# 2018_FDP_PROPULSION.net
KiCad netlist of a schematic drawn in Altium Designer
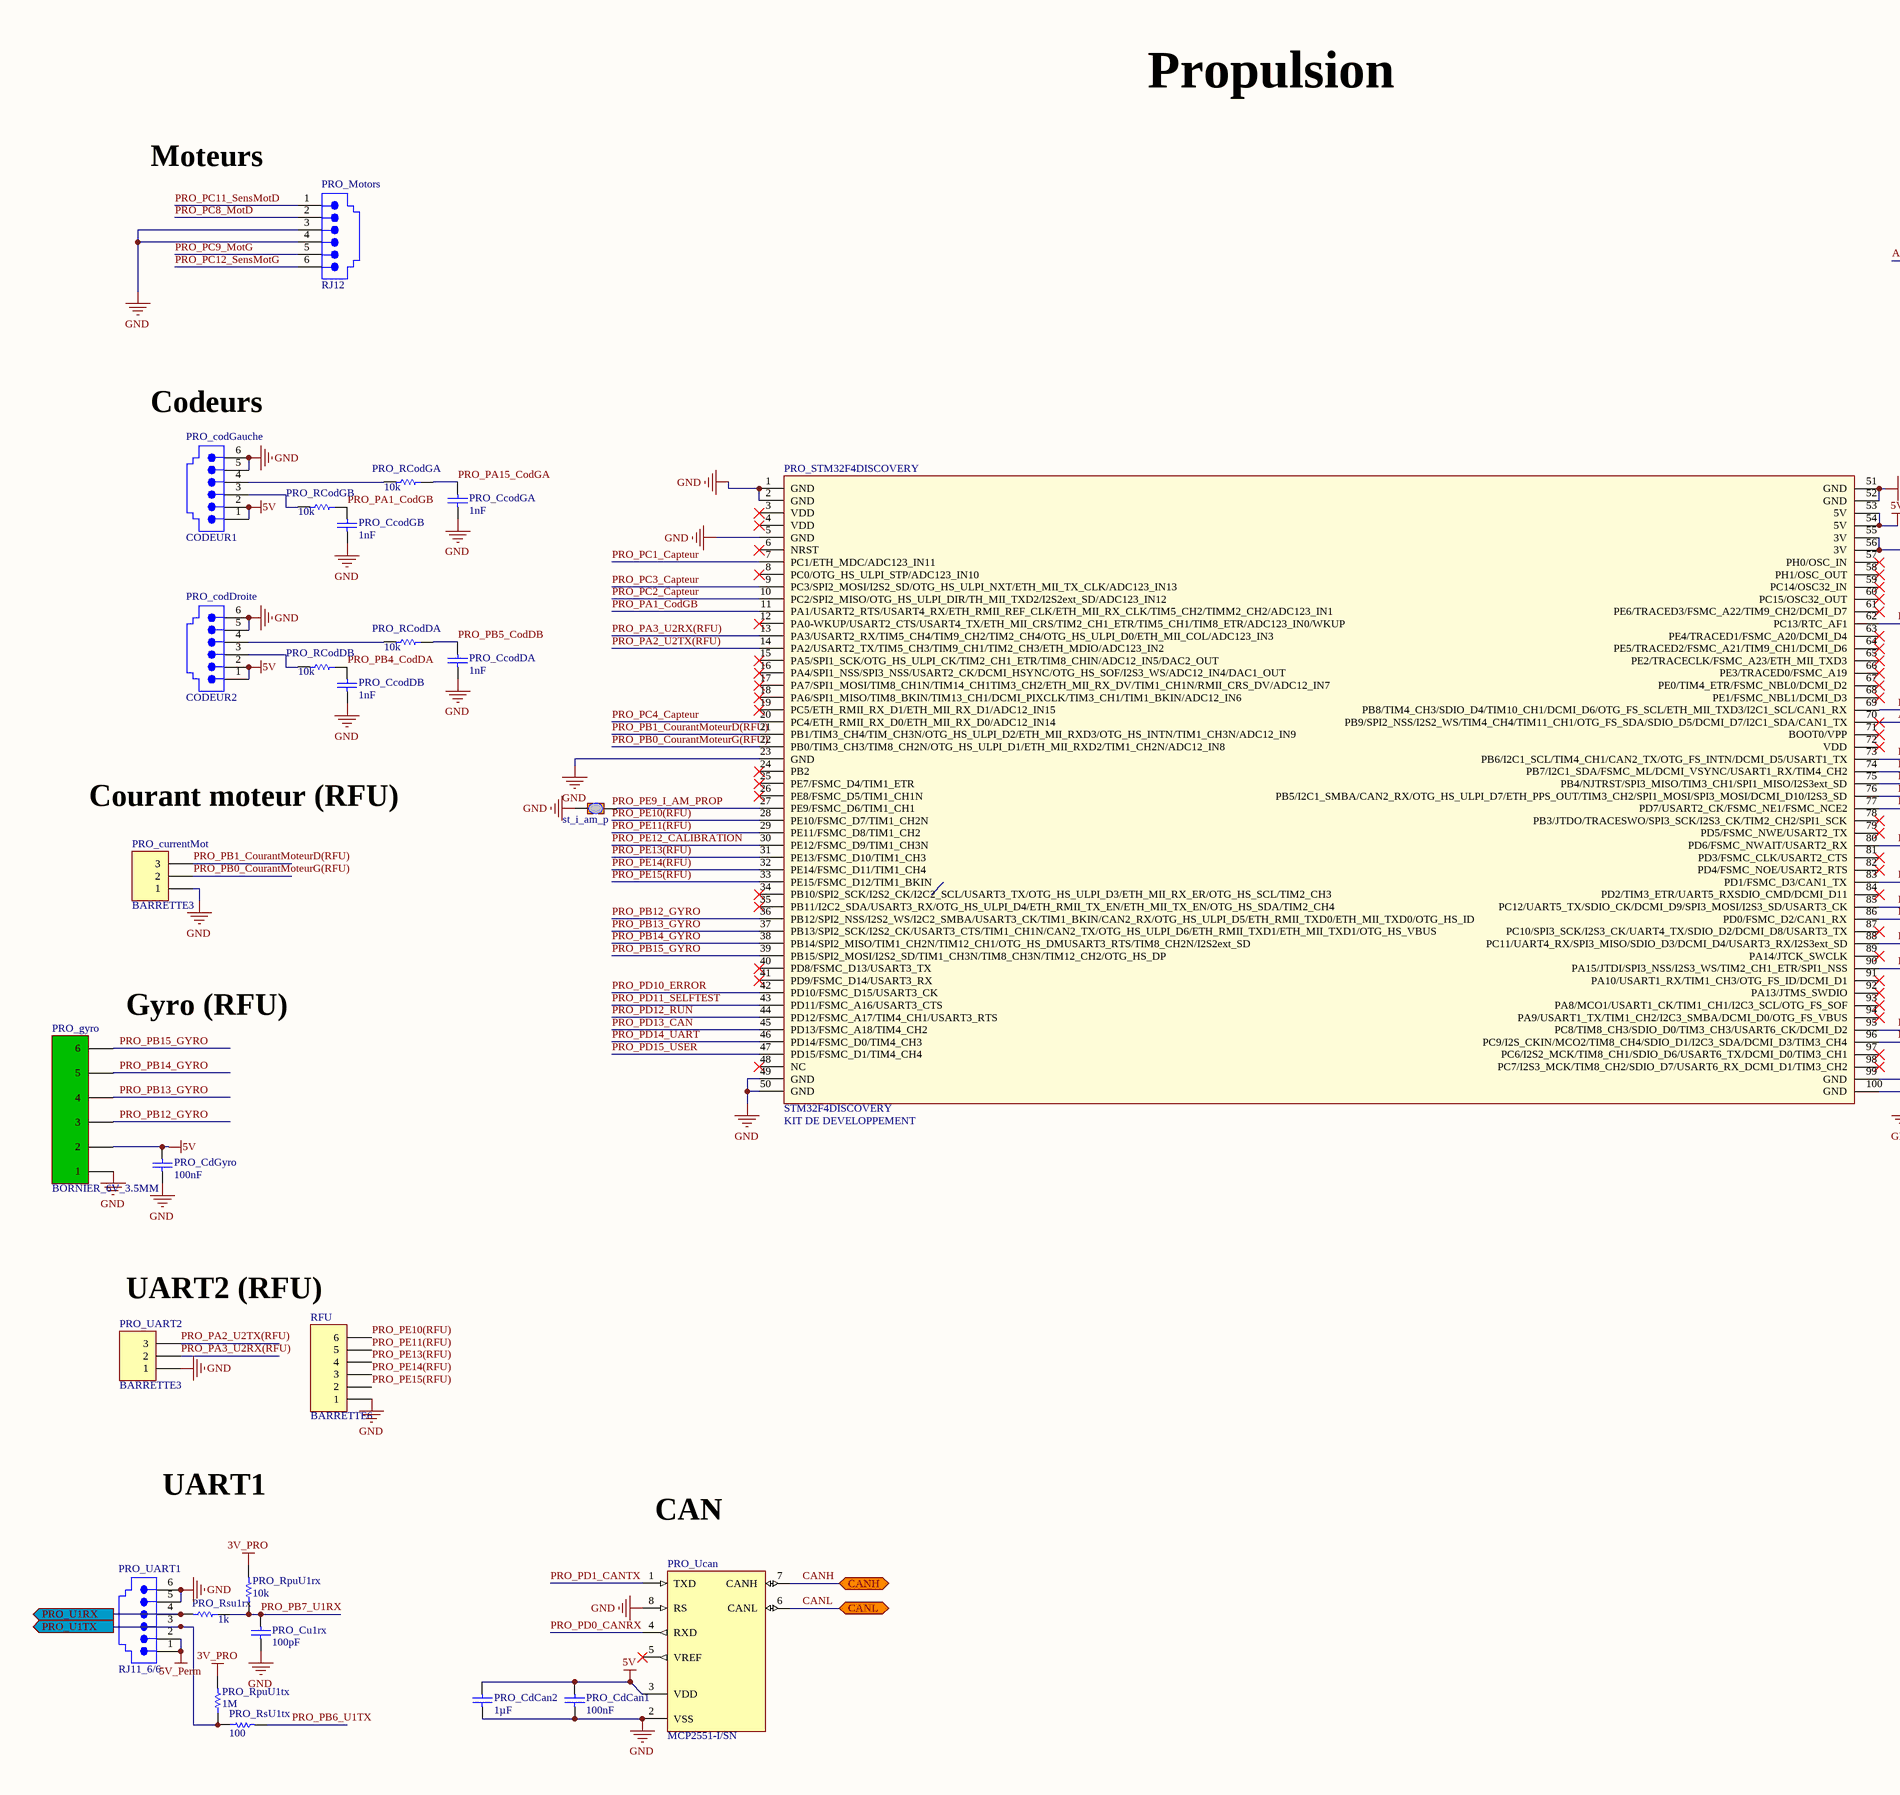
[diagram p0: 2018_FDP_PROPULSION.SchDoc, left]
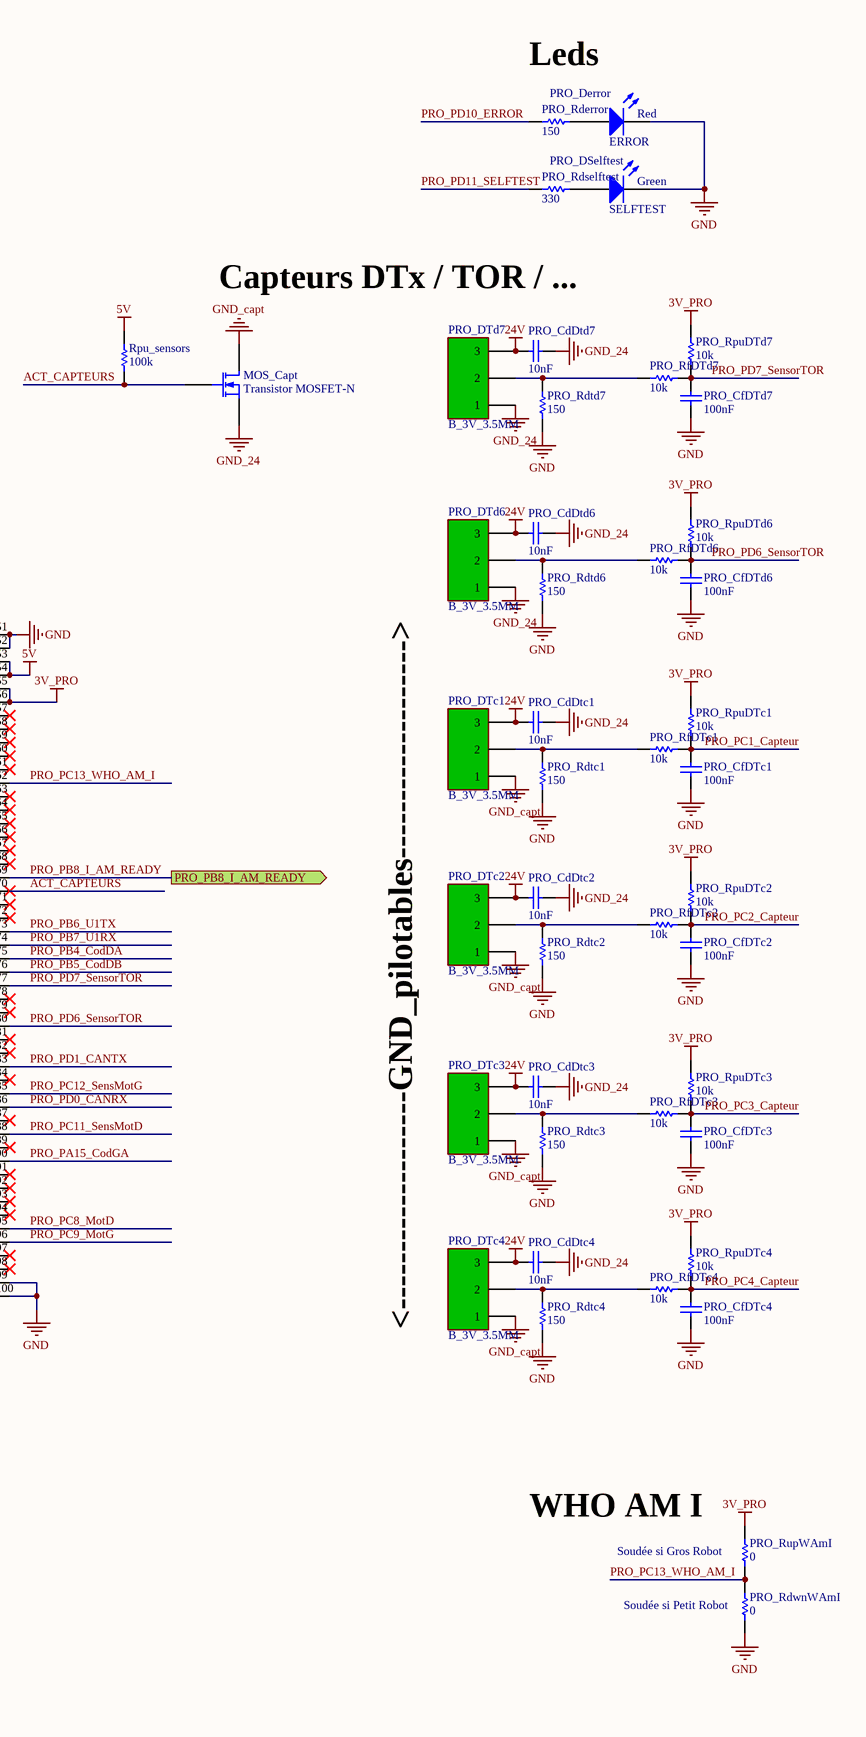
[diagram p1: 2018_FDP_PROPULSION.SchDoc, right]

(export (version "E")
  (design (tool "Eeschema 10.0.6"))
  (components
    (comp (ref "MOS_Capt")
      (value "Transistor MOSFET-N")
      (footprint "SOT23-3N")
      (description "N-Channel MOSFET")
      (fields (field (name "PUBLISHER") "Altium Limited"))
      (libsource (lib "_ROBOT") (part "Transistor MOSFET-N"))
    )
    (comp (ref "PRO_CcodDA")
      (value "1nF")
      (footprint "C0805_N")
      (description "Capacitor")
      (fields (field (name "PUBLISHER") "Altium Limited"))
      (libsource (lib "_ROBOT") (part "Condensateur"))
    )
    (comp (ref "PRO_CcodDB")
      (value "1nF")
      (footprint "C0805_N")
      (description "Capacitor")
      (fields (field (name "PUBLISHER") "Altium Limited"))
      (libsource (lib "_ROBOT") (part "Condensateur"))
    )
    (comp (ref "PRO_CcodGA")
      (value "1nF")
      (footprint "C0805_N")
      (description "Capacitor")
      (fields (field (name "PUBLISHER") "Altium Limited"))
      (libsource (lib "_ROBOT") (part "Condensateur"))
    )
    (comp (ref "PRO_CcodGB")
      (value "1nF")
      (footprint "C0805_N")
      (description "Capacitor")
      (fields (field (name "PUBLISHER") "Altium Limited"))
      (libsource (lib "_ROBOT") (part "Condensateur"))
    )
    (comp (ref "PRO_CdCan1")
      (value "100nF")
      (footprint "C0805_N")
      (description "Capacitor")
      (fields (field (name "PUBLISHER") "Altium Limited"))
      (libsource (lib "_ROBOT") (part "Condensateur"))
    )
    (comp (ref "PRO_CdCan2")
      (value "1µF")
      (footprint "C0805_N")
      (description "Capacitor")
      (fields (field (name "PUBLISHER") "Altium Limited"))
      (libsource (lib "_ROBOT") (part "Condensateur"))
    )
    (comp (ref "PRO_CdDtc1")
      (value "10nF")
      (footprint "C0805_N")
      (description "Capacitor")
      (fields (field (name "PUBLISHER") "Altium Limited"))
      (libsource (lib "_ROBOT") (part "Condensateur"))
    )
    (comp (ref "PRO_CdDtc2")
      (value "10nF")
      (footprint "C0805_N")
      (description "Capacitor")
      (fields (field (name "PUBLISHER") "Altium Limited"))
      (libsource (lib "_ROBOT") (part "Condensateur"))
    )
    (comp (ref "PRO_CdDtc3")
      (value "10nF")
      (footprint "C0805_N")
      (description "Capacitor")
      (fields (field (name "PUBLISHER") "Altium Limited"))
      (libsource (lib "_ROBOT") (part "Condensateur"))
    )
    (comp (ref "PRO_CdDtc4")
      (value "10nF")
      (footprint "C0805_N")
      (description "Capacitor")
      (fields (field (name "PUBLISHER") "Altium Limited"))
      (libsource (lib "_ROBOT") (part "Condensateur"))
    )
    (comp (ref "PRO_CdDtd6")
      (value "10nF")
      (footprint "C0805_N")
      (description "Capacitor")
      (fields (field (name "PUBLISHER") "Altium Limited"))
      (libsource (lib "_ROBOT") (part "Condensateur"))
    )
    (comp (ref "PRO_CdDtd7")
      (value "10nF")
      (footprint "C0805_N")
      (description "Capacitor")
      (fields (field (name "PUBLISHER") "Altium Limited"))
      (libsource (lib "_ROBOT") (part "Condensateur"))
    )
    (comp (ref "PRO_CdGyro")
      (value "100nF")
      (footprint "C0805_N")
      (description "Capacitor")
      (fields (field (name "PUBLISHER") "Altium Limited"))
      (libsource (lib "_ROBOT") (part "Condensateur"))
    )
    (comp (ref "PRO_CfDTc1")
      (value "100nF")
      (footprint "C0805_N")
      (description "Capacitor")
      (fields (field (name "PUBLISHER") "Altium Limited"))
      (libsource (lib "_ROBOT") (part "Condensateur"))
    )
    (comp (ref "PRO_CfDTc2")
      (value "100nF")
      (footprint "C0805_N")
      (description "Capacitor")
      (fields (field (name "PUBLISHER") "Altium Limited"))
      (libsource (lib "_ROBOT") (part "Condensateur"))
    )
    (comp (ref "PRO_CfDTc3")
      (value "100nF")
      (footprint "C0805_N")
      (description "Capacitor")
      (fields (field (name "PUBLISHER") "Altium Limited"))
      (libsource (lib "_ROBOT") (part "Condensateur"))
    )
    (comp (ref "PRO_CfDTc4")
      (value "100nF")
      (footprint "C0805_N")
      (description "Capacitor")
      (fields (field (name "PUBLISHER") "Altium Limited"))
      (libsource (lib "_ROBOT") (part "Condensateur"))
    )
    (comp (ref "PRO_CfDTd6")
      (value "100nF")
      (footprint "C0805_N")
      (description "Capacitor")
      (fields (field (name "PUBLISHER") "Altium Limited"))
      (libsource (lib "_ROBOT") (part "Condensateur"))
    )
    (comp (ref "PRO_CfDTd7")
      (value "100nF")
      (footprint "C0805_N")
      (description "Capacitor")
      (fields (field (name "PUBLISHER") "Altium Limited"))
      (libsource (lib "_ROBOT") (part "Condensateur"))
    )
    (comp (ref "PRO_codDroite")
      (value "CODEUR2")
      (footprint "RJ11_6/6 - droit")
      (description "Right Angle, Standard Profile, Offset Latch DECconnect, Flangeless PCB Jack")
      (fields (field (name "PUBLISHER") "Altium Limited"))
      (libsource (lib "miniprojet") (part "RJ11_6/6"))
    )
    (comp (ref "PRO_codGauche")
      (value "CODEUR1")
      (footprint "RJ11_6/6 - droit")
      (description "Right Angle, Standard Profile, Offset Latch DECconnect, Flangeless PCB Jack")
      (fields (field (name "PUBLISHER") "Altium Limited"))
      (libsource (lib "miniprojet") (part "RJ11_6/6"))
    )
    (comp (ref "PRO_Cu1rx")
      (value "100pF")
      (footprint "C0805_N")
      (description "Capacitor")
      (fields (field (name "PUBLISHER") "Altium Limited"))
      (libsource (lib "_ROBOT") (part "Condensateur"))
    )
    (comp (ref "PRO_currentMot")
      (value "BARRETTE3")
      (footprint "HE14_3")
      (description "Header, 3-Pin")
      (fields (field (name "PUBLISHER") "Altium Limited"))
      (libsource (lib "Connecteur") (part "BARRETTE3"))
    )
    (comp (ref "PRO_Derror")
      (value "ERROR")
      (footprint "LED_0805")
      (description "Typical LED")
      (fields (field (name "PUBLISHER") "Altium Limited"))
      (libsource (lib "_ROBOT") (part "LED"))
    )
    (comp (ref "PRO_DSelftest")
      (value "SELFTEST")
      (footprint "LED_0805")
      (description "Typical LED")
      (fields (field (name "PUBLISHER") "Altium Limited"))
      (libsource (lib "_ROBOT") (part "LED"))
    )
    (comp (ref "PRO_DTc1")
      (value "B_3V_3.5MM")
      (footprint "BORNIER_3V_3.5MM")
      (libsource (lib "Connecteur") (part "BORNIER_3V_3.5MM"))
    )
    (comp (ref "PRO_DTc2")
      (value "B_3V_3.5MM")
      (footprint "BORNIER_3V_3.5MM")
      (libsource (lib "Connecteur") (part "BORNIER_3V_3.5MM"))
    )
    (comp (ref "PRO_DTc3")
      (value "B_3V_3.5MM")
      (footprint "BORNIER_3V_3.5MM")
      (libsource (lib "Connecteur") (part "BORNIER_3V_3.5MM"))
    )
    (comp (ref "PRO_DTc4")
      (value "B_3V_3.5MM")
      (footprint "BORNIER_3V_3.5MM")
      (libsource (lib "Connecteur") (part "BORNIER_3V_3.5MM"))
    )
    (comp (ref "PRO_DTd6")
      (value "B_3V_3.5MM")
      (footprint "BORNIER_3V_3.5MM")
      (libsource (lib "Connecteur") (part "BORNIER_3V_3.5MM"))
    )
    (comp (ref "PRO_DTd7")
      (value "B_3V_3.5MM")
      (footprint "BORNIER_3V_3.5MM")
      (libsource (lib "Connecteur") (part "BORNIER_3V_3.5MM"))
    )
    (comp (ref "PRO_gyro")
      (value "BORNIER_6V_3.5MM")
      (footprint "BORNIER_6V_3.5MM")
      (libsource (lib "Connecteur") (part "BORNIER_6V_3.5MM"))
    )
    (comp (ref "PRO_Motors")
      (value "RJ12")
      (footprint "RJ11_6/6 - droit")
      (description "Right Angle, Standard Profile, Offset Latch DECconnect, Flangeless PCB Jack")
      (fields (field (name "PUBLISHER") "Altium Limited"))
      (libsource (lib "Connecteur") (part "RJ11_6/6"))
    )
    (comp (ref "PRO_RCodDA")
      (value "10k")
      (footprint "R1206_N")
      (description "Resistor")
      (fields (field (name "PUBLISHER") "Altium Limited"))
      (libsource (lib "_ROBOT") (part "Resistor"))
    )
    (comp (ref "PRO_RCodDB")
      (value "10k")
      (footprint "R1206_N")
      (description "Resistor")
      (fields (field (name "PUBLISHER") "Altium Limited"))
      (libsource (lib "_ROBOT") (part "Resistor"))
    )
    (comp (ref "PRO_RCodGA")
      (value "10k")
      (footprint "R1206_N")
      (description "Resistor")
      (fields (field (name "PUBLISHER") "Altium Limited"))
      (libsource (lib "_ROBOT") (part "Resistor"))
    )
    (comp (ref "PRO_RCodGB")
      (value "10k")
      (footprint "R1206_N")
      (description "Resistor")
      (fields (field (name "PUBLISHER") "Altium Limited"))
      (libsource (lib "_ROBOT") (part "Resistor"))
    )
    (comp (ref "PRO_Rderror")
      (value "150")
      (footprint "R1206_N")
      (description "Resistor")
      (fields (field (name "PUBLISHER") "Altium Limited"))
      (libsource (lib "_ROBOT") (part "Resistor"))
    )
    (comp (ref "PRO_Rdselftest")
      (value "330")
      (footprint "R1206_N")
      (description "Resistor")
      (fields (field (name "PUBLISHER") "Altium Limited"))
      (libsource (lib "_ROBOT") (part "Resistor"))
    )
    (comp (ref "PRO_Rdtc1")
      (value "150")
      (footprint "R1206_N")
      (description "Resistor")
      (fields (field (name "PUBLISHER") "Altium Limited"))
      (libsource (lib "_ROBOT") (part "Resistor"))
    )
    (comp (ref "PRO_Rdtc2")
      (value "150")
      (footprint "R1206_N")
      (description "Resistor")
      (fields (field (name "PUBLISHER") "Altium Limited"))
      (libsource (lib "_ROBOT") (part "Resistor"))
    )
    (comp (ref "PRO_Rdtc3")
      (value "150")
      (footprint "R1206_N")
      (description "Resistor")
      (fields (field (name "PUBLISHER") "Altium Limited"))
      (libsource (lib "_ROBOT") (part "Resistor"))
    )
    (comp (ref "PRO_Rdtc4")
      (value "150")
      (footprint "R1206_N")
      (description "Resistor")
      (fields (field (name "PUBLISHER") "Altium Limited"))
      (libsource (lib "_ROBOT") (part "Resistor"))
    )
    (comp (ref "PRO_Rdtd6")
      (value "150")
      (footprint "R1206_N")
      (description "Resistor")
      (fields (field (name "PUBLISHER") "Altium Limited"))
      (libsource (lib "_ROBOT") (part "Resistor"))
    )
    (comp (ref "PRO_Rdtd7")
      (value "150")
      (footprint "R1206_N")
      (description "Resistor")
      (fields (field (name "PUBLISHER") "Altium Limited"))
      (libsource (lib "_ROBOT") (part "Resistor"))
    )
    (comp (ref "PRO_RdwnWAmI")
      (value "0")
      (footprint "R1206_N")
      (description "Resistor")
      (fields (field (name "PUBLISHER") "Altium Limited"))
      (libsource (lib "_ROBOT") (part "Resistor"))
    )
    (comp (ref "PRO_RfDTc1")
      (value "10k")
      (footprint "R1206_N")
      (description "Resistor")
      (fields (field (name "PUBLISHER") "Altium Limited"))
      (libsource (lib "_ROBOT") (part "Resistor"))
    )
    (comp (ref "PRO_RfDTc2")
      (value "10k")
      (footprint "R1206_N")
      (description "Resistor")
      (fields (field (name "PUBLISHER") "Altium Limited"))
      (libsource (lib "_ROBOT") (part "Resistor"))
    )
    (comp (ref "PRO_RfDTc3")
      (value "10k")
      (footprint "R1206_N")
      (description "Resistor")
      (fields (field (name "PUBLISHER") "Altium Limited"))
      (libsource (lib "_ROBOT") (part "Resistor"))
    )
    (comp (ref "PRO_RfDTc4")
      (value "10k")
      (footprint "R1206_N")
      (description "Resistor")
      (fields (field (name "PUBLISHER") "Altium Limited"))
      (libsource (lib "_ROBOT") (part "Resistor"))
    )
    (comp (ref "PRO_RfDTd6")
      (value "10k")
      (footprint "R1206_N")
      (description "Resistor")
      (fields (field (name "PUBLISHER") "Altium Limited"))
      (libsource (lib "_ROBOT") (part "Resistor"))
    )
    (comp (ref "PRO_RfDTd7")
      (value "10k")
      (footprint "R1206_N")
      (description "Resistor")
      (fields (field (name "PUBLISHER") "Altium Limited"))
      (libsource (lib "_ROBOT") (part "Resistor"))
    )
    (comp (ref "PRO_RpuDTc1")
      (value "10k")
      (footprint "R1206_N")
      (description "Resistor")
      (fields (field (name "PUBLISHER") "Altium Limited"))
      (libsource (lib "_ROBOT") (part "Resistor"))
    )
    (comp (ref "PRO_RpuDTc2")
      (value "10k")
      (footprint "R1206_N")
      (description "Resistor")
      (fields (field (name "PUBLISHER") "Altium Limited"))
      (libsource (lib "_ROBOT") (part "Resistor"))
    )
    (comp (ref "PRO_RpuDTc3")
      (value "10k")
      (footprint "R1206_N")
      (description "Resistor")
      (fields (field (name "PUBLISHER") "Altium Limited"))
      (libsource (lib "_ROBOT") (part "Resistor"))
    )
    (comp (ref "PRO_RpuDTc4")
      (value "10k")
      (footprint "R1206_N")
      (description "Resistor")
      (fields (field (name "PUBLISHER") "Altium Limited"))
      (libsource (lib "_ROBOT") (part "Resistor"))
    )
    (comp (ref "PRO_RpuDTd6")
      (value "10k")
      (footprint "R1206_N")
      (description "Resistor")
      (fields (field (name "PUBLISHER") "Altium Limited"))
      (libsource (lib "_ROBOT") (part "Resistor"))
    )
    (comp (ref "PRO_RpuDTd7")
      (value "10k")
      (footprint "R1206_N")
      (description "Resistor")
      (fields (field (name "PUBLISHER") "Altium Limited"))
      (libsource (lib "_ROBOT") (part "Resistor"))
    )
    (comp (ref "PRO_RpuU1rx")
      (value "10k")
      (footprint "R1206_N")
      (description "Resistor")
      (fields (field (name "PUBLISHER") "Altium Limited"))
      (libsource (lib "_ROBOT") (part "Resistor"))
    )
    (comp (ref "PRO_RpuU1tx")
      (value "1M")
      (footprint "R1206_N")
      (description "Resistor")
      (fields (field (name "PUBLISHER") "Altium Limited"))
      (libsource (lib "_ROBOT") (part "Resistor"))
    )
    (comp (ref "PRO_Rsu1rx")
      (value "1k")
      (footprint "R1206_N")
      (description "Resistor")
      (fields (field (name "PUBLISHER") "Altium Limited"))
      (libsource (lib "_ROBOT") (part "Resistor"))
    )
    (comp (ref "PRO_RsU1tx")
      (value "100")
      (footprint "R1206_N")
      (description "Resistor")
      (fields (field (name "PUBLISHER") "Altium Limited"))
      (libsource (lib "_ROBOT") (part "Resistor"))
    )
    (comp (ref "PRO_RupWAmI")
      (value "0")
      (footprint "R1206_N")
      (description "Resistor")
      (fields (field (name "PUBLISHER") "Altium Limited"))
      (libsource (lib "_ROBOT") (part "Resistor"))
    )
    (comp (ref "PRO_STM32F4DISCOVERY")
      (value "STM32F4DISCOVERY")
      (footprint "STM32_F4DISCOVERY")
      (description "KIT DE DEVELOPPEMENT POUR MICROCONTROLEUR STM32F407VGT6")
      (fields (field (name "TYPE") "KIT DE DEVELOPPEMENT"))
      (libsource (lib "circuits integres") (part "STM32F4DISCOVERY"))
    )
    (comp (ref "PRO_UART1")
      (value "RJ11_6/6")
      (footprint "RJ11_6/6 - droit")
      (description "Right Angle, Standard Profile, Offset Latch DECconnect, Flangeless PCB Jack")
      (fields (field (name "PUBLISHER") "Altium Limited"))
      (libsource (lib "Connecteur") (part "RJ11_6/6"))
    )
    (comp (ref "PRO_UART2")
      (value "BARRETTE3")
      (footprint "HE14_3")
      (description "Header, 3-Pin")
      (fields (field (name "PUBLISHER") "Altium Limited"))
      (libsource (lib "Connecteur") (part "BARRETTE3"))
    )
    (comp (ref "PRO_Ucan")
      (value "MCP2551-I/SN")
      (footprint "SO8_N")
      (description "High-Speed CAN Transceiver, 8-Pin SOIC, Industrial Temperature")
      (fields (field (name "PUBLISHER") "Damien Guitton"))
      (libsource (lib "Circuit intégré") (part "MCP2551-I/SN"))
    )
    (comp (ref "RFU")
      (value "BARRETTE6")
      (footprint "HE14_6")
      (description "Header, 6-Pin")
      (fields (field (name "PUBLISHER") "Altium Limited"))
      (libsource (lib "Connecteur") (part "BARRETTE6"))
    )
    (comp (ref "Rpu_sensors")
      (value "100k")
      (footprint "R1206_N")
      (description "Resistor")
      (fields (field (name "PUBLISHER") "Altium Limited"))
      (libsource (lib "_ROBOT") (part "Resistor"))
    )
    (comp (ref "st_i_am_p")
      (value "Goutte Strap_2")
      (footprint "Goutte Strap_2 Pads_Clearance 0.254mm")
      (fields (field (name "PUBLISHER") "Damien Guitton"))
      (libsource (lib "DG_Connecteur") (part "Goutte Strap_2"))
    )
  )
  (nets
    (net (code "1") (name "/ACT_CAPTEURS") (class "Default")
      (node (ref "MOS_Capt") (pin "1") (pinfunction "G_1") (pintype "passive"))
      (node (ref "PRO_STM32F4DISCOVERY") (pin "70") (pinfunction "PB9/SPI2_NSS/I2S2_WS/TIM4_CH4/TIM11_CH1/OTG_FS_SDA/SDIO_D5/DCMI_D7/I2C1_SDA/CAN1_TX_70") (pintype "passive"))
      (node (ref "Rpu_sensors") (pin "1") (pinfunction "1_1") (pintype "passive"))
    )
    (net (code "2") (name "/CANH") (class "Default")
      (node (ref "PRO_Ucan") (pin "7") (pinfunction "CANH_7") (pintype "bidirectional"))
    )
    (net (code "3") (name "/CANL") (class "Default")
      (node (ref "PRO_Ucan") (pin "6") (pinfunction "CANL_6") (pintype "bidirectional"))
    )
    (net (code "4") (name "/PRO_PA1_CodGB") (class "Default")
      (node (ref "PRO_CcodGB") (pin "2") (pinfunction "2_2") (pintype "passive"))
      (node (ref "PRO_RCodGB") (pin "1") (pinfunction "1_1") (pintype "passive"))
      (node (ref "PRO_STM32F4DISCOVERY") (pin "11") (pinfunction "PA1/USART2_RTS/USART4_RX/ETH_RMII_REF_CLK/ETH_MII_RX_CLK/TIM5_CH2/TIMM2_CH2/ADC123_IN1_11") (pintype "passive"))
    )
    (net (code "5") (name "/PRO_PA2_U2TX(RFU)") (class "Default")
      (node (ref "PRO_STM32F4DISCOVERY") (pin "14") (pinfunction "PA2/USART2_TX/TIM5_CH3/TIM9_CH1/TIM2_CH3/ETH_MDIO/ADC123_IN2_14") (pintype "passive"))
      (node (ref "PRO_UART2") (pin "3") (pinfunction "3_3") (pintype "passive"))
    )
    (net (code "6") (name "/PRO_PA3_U2RX(RFU)") (class "Default")
      (node (ref "PRO_STM32F4DISCOVERY") (pin "13") (pinfunction "PA3/USART2_RX/TIM5_CH4/TIM9_CH2/TIM2_CH4/OTG_HS_ULPI_D0/ETH_MII_COL/ADC123_IN3_13") (pintype "passive"))
      (node (ref "PRO_UART2") (pin "2") (pinfunction "2_2") (pintype "passive"))
    )
    (net (code "7") (name "/PRO_PA15_CodGA") (class "Default")
      (node (ref "PRO_CcodGA") (pin "2") (pinfunction "2_2") (pintype "passive"))
      (node (ref "PRO_RCodGA") (pin "1") (pinfunction "1_1") (pintype "passive"))
      (node (ref "PRO_STM32F4DISCOVERY") (pin "90") (pinfunction "PA15/JTDI/SPI3_NSS/I2S3_WS/TIM2_CH1_ETR/SPI1_NSS_90") (pintype "passive"))
    )
    (net (code "8") (name "/PRO_PB0_CourantMoteurG(RFU)") (class "Default")
      (node (ref "PRO_STM32F4DISCOVERY") (pin "22") (pinfunction "PB0/TIM3_CH3/TIM8_CH2N/OTG_HS_ULPI_D1/ETH_MII_RXD2/TIM1_CH2N/ADC12_IN8_22") (pintype "passive"))
      (node (ref "PRO_currentMot") (pin "2") (pinfunction "2_2") (pintype "passive"))
    )
    (net (code "9") (name "/PRO_PB1_CourantMoteurD(RFU)") (class "Default")
      (node (ref "PRO_STM32F4DISCOVERY") (pin "21") (pinfunction "PB1/TIM3_CH4/TIM_CH3N/OTG_HS_ULPI_D2/ETH_MII_RXD3/OTG_HS_INTN/TIM1_CH3N/ADC12_IN9_21") (pintype "passive"))
      (node (ref "PRO_currentMot") (pin "3") (pinfunction "3_3") (pintype "passive"))
    )
    (net (code "10") (name "/PRO_PB4_CodDA") (class "Default")
      (node (ref "PRO_CcodDB") (pin "2") (pinfunction "2_2") (pintype "passive"))
      (node (ref "PRO_RCodDB") (pin "1") (pinfunction "1_1") (pintype "passive"))
      (node (ref "PRO_STM32F4DISCOVERY") (pin "75") (pinfunction "PB4/NJTRST/SPI3_MISO/TIM3_CH1/SPI1_MISO/I2S3ext_SD_75") (pintype "passive"))
    )
    (net (code "11") (name "/PRO_PB5_CodDB") (class "Default")
      (node (ref "PRO_CcodDA") (pin "2") (pinfunction "2_2") (pintype "passive"))
      (node (ref "PRO_RCodDA") (pin "1") (pinfunction "1_1") (pintype "passive"))
      (node (ref "PRO_STM32F4DISCOVERY") (pin "76") (pinfunction "PB5/I2C1_SMBA/CAN2_RX/OTG_HS_ULPI_D7/ETH_PPS_OUT/TIM3_CH2/SPI1_MOSI/SPI3_MOSI/DCMI_D10/I2S3_SD_76") (pintype "passive"))
    )
    (net (code "12") (name "/PRO_PB6_U1TX") (class "Default")
      (node (ref "PRO_RsU1tx") (pin "2") (pinfunction "2_2") (pintype "passive"))
      (node (ref "PRO_STM32F4DISCOVERY") (pin "73") (pinfunction "PB6/I2C1_SCL/TIM4_CH1/CAN2_TX/OTG_FS_INTN/DCMI_D5/USART1_TX_73") (pintype "passive"))
    )
    (net (code "13") (name "/PRO_PB7_U1RX") (class "Default")
      (node (ref "PRO_Cu1rx") (pin "2") (pinfunction "2_2") (pintype "passive"))
      (node (ref "PRO_RpuU1rx") (pin "1") (pinfunction "1_1") (pintype "passive"))
      (node (ref "PRO_Rsu1rx") (pin "1") (pinfunction "1_1") (pintype "passive"))
      (node (ref "PRO_STM32F4DISCOVERY") (pin "74") (pinfunction "PB7/I2C1_SDA/FSMC_ML/DCMI_VSYNC/USART1_RX/TIM4_CH2_74") (pintype "passive"))
    )
    (net (code "14") (name "/PRO_PB8_I_AM_READY") (class "Default")
      (node (ref "PRO_STM32F4DISCOVERY") (pin "69") (pinfunction "PB8/TIM4_CH3/SDIO_D4/TIM10_CH1/DCMI_D6/OTG_FS_SCL/ETH_MII_TXD3/I2C1_SCL/CAN1_RX_69") (pintype "passive"))
    )
    (net (code "15") (name "/PRO_PB12_GYRO") (class "Default")
      (node (ref "PRO_STM32F4DISCOVERY") (pin "36") (pinfunction "PB12/SPI2_NSS/I2S2_WS/I2C2_SMBA/USART3_CK/TIM1_BKIN/CAN2_RX/OTG_HS_ULPI_D5/ETH_RMII_TXD0/ETH_MII_TXD0/OTG_HS_ID_36") (pintype "passive"))
      (node (ref "PRO_gyro") (pin "3") (pinfunction "3_3") (pintype "passive"))
    )
    (net (code "16") (name "/PRO_PB13_GYRO") (class "Default")
      (node (ref "PRO_STM32F4DISCOVERY") (pin "37") (pinfunction "PB13/SPI2_SCK/I2S2_CK/USART3_CTS/TIM1_CH1N/CAN2_TX/OTG_HS_ULPI_D6/ETH_RMII_TXD1/ETH_MII_TXD1/OTG_HS_VBUS_37") (pintype "passive"))
      (node (ref "PRO_gyro") (pin "4") (pinfunction "4_4") (pintype "passive"))
    )
    (net (code "17") (name "/PRO_PB14_GYRO") (class "Default")
      (node (ref "PRO_STM32F4DISCOVERY") (pin "38") (pinfunction "PB14/SPI2_MISO/TIM1_CH2N/TIM12_CH1/OTG_HS_DMUSART3_RTS/TIM8_CH2N/I2S2ext_SD_38") (pintype "passive"))
      (node (ref "PRO_gyro") (pin "5") (pinfunction "5_5") (pintype "passive"))
    )
    (net (code "18") (name "/PRO_PB15_GYRO") (class "Default")
      (node (ref "PRO_STM32F4DISCOVERY") (pin "39") (pinfunction "PB15/SPI2_MOSI/I2S2_SD/TIM1_CH3N/TIM8_CH3N/TIM12_CH2/OTG_HS_DP_39") (pintype "passive"))
      (node (ref "PRO_gyro") (pin "6") (pinfunction "6_6") (pintype "passive"))
    )
    (net (code "19") (name "/PRO_PC1_Capteur") (class "Default")
      (node (ref "PRO_CfDTc1") (pin "2") (pinfunction "2_2") (pintype "passive"))
      (node (ref "PRO_RfDTc1") (pin "2") (pinfunction "2_2") (pintype "passive"))
      (node (ref "PRO_RpuDTc1") (pin "1") (pinfunction "1_1") (pintype "passive"))
      (node (ref "PRO_STM32F4DISCOVERY") (pin "7") (pinfunction "PC1/ETH_MDC/ADC123_IN11_7") (pintype "passive"))
    )
    (net (code "20") (name "/PRO_PC2_Capteur") (class "Default")
      (node (ref "PRO_CfDTc2") (pin "2") (pinfunction "2_2") (pintype "passive"))
      (node (ref "PRO_RfDTc2") (pin "2") (pinfunction "2_2") (pintype "passive"))
      (node (ref "PRO_RpuDTc2") (pin "1") (pinfunction "1_1") (pintype "passive"))
      (node (ref "PRO_STM32F4DISCOVERY") (pin "10") (pinfunction "PC2/SPI2_MISO/OTG_HS_ULPI_DIR/TH_MII_TXD2/I2S2ext_SD/ADC123_IN12_10") (pintype "passive"))
    )
    (net (code "21") (name "/PRO_PC3_Capteur") (class "Default")
      (node (ref "PRO_CfDTc3") (pin "2") (pinfunction "2_2") (pintype "passive"))
      (node (ref "PRO_RfDTc3") (pin "2") (pinfunction "2_2") (pintype "passive"))
      (node (ref "PRO_RpuDTc3") (pin "1") (pinfunction "1_1") (pintype "passive"))
      (node (ref "PRO_STM32F4DISCOVERY") (pin "9") (pinfunction "PC3/SPI2_MOSI/I2S2_SD/OTG_HS_ULPI_NXT/ETH_MII_TX_CLK/ADC123_IN13_9") (pintype "passive"))
    )
    (net (code "22") (name "/PRO_PC4_Capteur") (class "Default")
      (node (ref "PRO_CfDTc4") (pin "2") (pinfunction "2_2") (pintype "passive"))
      (node (ref "PRO_RfDTc4") (pin "2") (pinfunction "2_2") (pintype "passive"))
      (node (ref "PRO_RpuDTc4") (pin "1") (pinfunction "1_1") (pintype "passive"))
      (node (ref "PRO_STM32F4DISCOVERY") (pin "20") (pinfunction "PC4/ETH_RMII_RX_D0/ETH_MII_RX_D0/ADC12_IN14_20") (pintype "passive"))
    )
    (net (code "23") (name "/PRO_PC8_MotD") (class "Default")
      (node (ref "PRO_Motors") (pin "2") (pinfunction "2_2") (pintype "passive"))
      (node (ref "PRO_STM32F4DISCOVERY") (pin "95") (pinfunction "PC8/TIM8_CH3/SDIO_D0/TIM3_CH3/USART6_CK/DCMI_D2_95") (pintype "passive"))
    )
    (net (code "24") (name "/PRO_PC9_MotG") (class "Default")
      (node (ref "PRO_Motors") (pin "5") (pinfunction "5_5") (pintype "passive"))
      (node (ref "PRO_STM32F4DISCOVERY") (pin "96") (pinfunction "PC9/I2S_CKIN/MCO2/TIM8_CH4/SDIO_D1/I2C3_SDA/DCMI_D3/TIM3_CH4_96") (pintype "passive"))
    )
    (net (code "25") (name "/PRO_PC11_SensMotD") (class "Default")
      (node (ref "PRO_Motors") (pin "1") (pinfunction "1_1") (pintype "passive"))
      (node (ref "PRO_STM32F4DISCOVERY") (pin "88") (pinfunction "PC11/UART4_RX/SPI3_MISO/SDIO_D3/DCMI_D4/USART3_RX/I2S3ext_SD_88") (pintype "passive"))
    )
    (net (code "26") (name "/PRO_PC12_SensMotG") (class "Default")
      (node (ref "PRO_Motors") (pin "6") (pinfunction "6_6") (pintype "passive"))
      (node (ref "PRO_STM32F4DISCOVERY") (pin "85") (pinfunction "PC12/UART5_TX/SDIO_CK/DCMI_D9/SPI3_MOSI/I2S3_SD/USART3_CK_85") (pintype "passive"))
    )
    (net (code "27") (name "/PRO_PC13_WHO_AM_I") (class "Default")
      (node (ref "PRO_RdwnWAmI") (pin "2") (pinfunction "2_2") (pintype "passive"))
      (node (ref "PRO_RupWAmI") (pin "1") (pinfunction "1_1") (pintype "passive"))
      (node (ref "PRO_STM32F4DISCOVERY") (pin "62") (pinfunction "PC13/RTC_AF1_62") (pintype "passive"))
    )
    (net (code "28") (name "/PRO_PD0_CANRX") (class "Default")
      (node (ref "PRO_STM32F4DISCOVERY") (pin "86") (pinfunction "PD0/FSMC_D2/CAN1_RX_86") (pintype "passive"))
      (node (ref "PRO_Ucan") (pin "4") (pinfunction "RXD_4") (pintype "output"))
    )
    (net (code "29") (name "/PRO_PD1_CANTX") (class "Default")
      (node (ref "PRO_STM32F4DISCOVERY") (pin "83") (pinfunction "PD1/FSMC_D3/CAN1_TX_83") (pintype "passive"))
      (node (ref "PRO_Ucan") (pin "1") (pinfunction "TXD_1") (pintype "input"))
    )
    (net (code "30") (name "/PRO_PD6_SensorTOR") (class "Default")
      (node (ref "PRO_CfDTd6") (pin "2") (pinfunction "2_2") (pintype "passive"))
      (node (ref "PRO_RfDTd6") (pin "2") (pinfunction "2_2") (pintype "passive"))
      (node (ref "PRO_RpuDTd6") (pin "1") (pinfunction "1_1") (pintype "passive"))
      (node (ref "PRO_STM32F4DISCOVERY") (pin "80") (pinfunction "PD6/FSMC_NWAIT/USART2_RX_80") (pintype "passive"))
    )
    (net (code "31") (name "/PRO_PD7_SensorTOR") (class "Default")
      (node (ref "PRO_CfDTd7") (pin "2") (pinfunction "2_2") (pintype "passive"))
      (node (ref "PRO_RfDTd7") (pin "2") (pinfunction "2_2") (pintype "passive"))
      (node (ref "PRO_RpuDTd7") (pin "1") (pinfunction "1_1") (pintype "passive"))
      (node (ref "PRO_STM32F4DISCOVERY") (pin "77") (pinfunction "PD7/USART2_CK/FSMC_NE1/FSMC_NCE2_77") (pintype "passive"))
    )
    (net (code "32") (name "/PRO_PD10_ERROR") (class "Default")
      (node (ref "PRO_Rderror") (pin "1") (pinfunction "1_1") (pintype "passive"))
      (node (ref "PRO_STM32F4DISCOVERY") (pin "42") (pinfunction "PD10/FSMC_D15/USART3_CK_42") (pintype "passive"))
    )
    (net (code "33") (name "/PRO_PD11_SELFTEST") (class "Default")
      (node (ref "PRO_Rdselftest") (pin "1") (pinfunction "1_1") (pintype "passive"))
      (node (ref "PRO_STM32F4DISCOVERY") (pin "43") (pinfunction "PD11/FSMC_A16/USART3_CTS_43") (pintype "passive"))
    )
    (net (code "34") (name "/PRO_PD12_RUN") (class "Default")
      (node (ref "PRO_STM32F4DISCOVERY") (pin "44") (pinfunction "PD12/FSMC_A17/TIM4_CH1/USART3_RTS_44") (pintype "passive"))
    )
    (net (code "35") (name "/PRO_PD13_CAN") (class "Default")
      (node (ref "PRO_STM32F4DISCOVERY") (pin "45") (pinfunction "PD13/FSMC_A18/TIM4_CH2_45") (pintype "passive"))
    )
    (net (code "36") (name "/PRO_PD14_UART") (class "Default")
      (node (ref "PRO_STM32F4DISCOVERY") (pin "46") (pinfunction "PD14/FSMC_D0/TIM4_CH3_46") (pintype "passive"))
    )
    (net (code "37") (name "/PRO_PD15_USER") (class "Default")
      (node (ref "PRO_STM32F4DISCOVERY") (pin "47") (pinfunction "PD15/FSMC_D1/TIM4_CH4_47") (pintype "passive"))
    )
    (net (code "39") (name "/PRO_PE10(RFU)") (class "Default")
      (node (ref "PRO_STM32F4DISCOVERY") (pin "28") (pinfunction "PE10/FSMC_D7/TIM1_CH2N_28") (pintype "passive"))
      (node (ref "RFU") (pin "6") (pinfunction "6_6") (pintype "passive"))
    )
    (net (code "40") (name "/PRO_PE11(RFU)") (class "Default")
      (node (ref "PRO_STM32F4DISCOVERY") (pin "29") (pinfunction "PE11/FSMC_D8/TIM1_CH2_29") (pintype "passive"))
      (node (ref "RFU") (pin "5") (pinfunction "5_5") (pintype "passive"))
    )
    (net (code "41") (name "/PRO_PE12_CALIBRATION") (class "Default")
      (node (ref "PRO_STM32F4DISCOVERY") (pin "30") (pinfunction "PE12/FSMC_D9/TIM1_CH3N_30") (pintype "passive"))
    )
    (net (code "42") (name "/PRO_PE13(RFU)") (class "Default")
      (node (ref "PRO_STM32F4DISCOVERY") (pin "31") (pinfunction "PE13/FSMC_D10/TIM1_CH3_31") (pintype "passive"))
      (node (ref "RFU") (pin "4") (pinfunction "4_4") (pintype "passive"))
    )
    (net (code "43") (name "/PRO_PE14(RFU)") (class "Default")
      (node (ref "PRO_STM32F4DISCOVERY") (pin "32") (pinfunction "PE14/FSMC_D11/TIM1_CH4_32") (pintype "passive"))
      (node (ref "RFU") (pin "3") (pinfunction "3_3") (pintype "passive"))
    )
    (net (code "44") (name "/PRO_PE15(RFU)") (class "Default")
      (node (ref "PRO_STM32F4DISCOVERY") (pin "33") (pinfunction "PE15/FSMC_D12/TIM1_BKIN_33") (pintype "passive"))
      (node (ref "RFU") (pin "2") (pinfunction "2_2") (pintype "passive"))
    )
    (net (code "45") (name "/PRO_U1RX") (class "Default")
      (node (ref "PRO_Rsu1rx") (pin "2") (pinfunction "2_2") (pintype "passive"))
      (node (ref "PRO_UART1") (pin "4") (pinfunction "4_4") (pintype "passive"))
    )
    (net (code "46") (name "/PRO_U1TX") (class "Default")
      (node (ref "PRO_RpuU1tx") (pin "1") (pinfunction "1_1") (pintype "passive"))
      (node (ref "PRO_RsU1tx") (pin "1") (pinfunction "1_1") (pintype "passive"))
      (node (ref "PRO_UART1") (pin "3") (pinfunction "3_3") (pintype "passive"))
    )
    (net (code "47") (name "3V_PRO") (class "Default")
      (node (ref "PRO_RpuDTc1") (pin "2") (pinfunction "2_2") (pintype "passive"))
      (node (ref "PRO_RpuDTc2") (pin "2") (pinfunction "2_2") (pintype "passive"))
      (node (ref "PRO_RpuDTc3") (pin "2") (pinfunction "2_2") (pintype "passive"))
      (node (ref "PRO_RpuDTc4") (pin "2") (pinfunction "2_2") (pintype "passive"))
      (node (ref "PRO_RpuDTd6") (pin "2") (pinfunction "2_2") (pintype "passive"))
      (node (ref "PRO_RpuDTd7") (pin "2") (pinfunction "2_2") (pintype "passive"))
      (node (ref "PRO_RpuU1rx") (pin "2") (pinfunction "2_2") (pintype "passive"))
      (node (ref "PRO_RpuU1tx") (pin "2") (pinfunction "2_2") (pintype "passive"))
      (node (ref "PRO_RupWAmI") (pin "2") (pinfunction "2_2") (pintype "passive"))
      (node (ref "PRO_STM32F4DISCOVERY") (pin "55") (pinfunction "3V_55") (pintype "passive"))
      (node (ref "PRO_STM32F4DISCOVERY") (pin "56") (pinfunction "3V_56") (pintype "passive"))
    )
    (net (code "48") (name "5V") (class "Default")
      (node (ref "PRO_CdCan1") (pin "2") (pinfunction "2_2") (pintype "passive"))
      (node (ref "PRO_CdCan2") (pin "2") (pinfunction "2_2") (pintype "passive"))
      (node (ref "PRO_CdGyro") (pin "2") (pinfunction "2_2") (pintype "passive"))
      (node (ref "PRO_STM32F4DISCOVERY") (pin "53") (pinfunction "5V_53") (pintype "passive"))
      (node (ref "PRO_STM32F4DISCOVERY") (pin "54") (pinfunction "5V_54") (pintype "passive"))
      (node (ref "PRO_Ucan") (pin "3") (pinfunction "VDD_3") (pintype "power_in"))
      (node (ref "PRO_codDroite") (pin "1") (pinfunction "1_1") (pintype "passive"))
      (node (ref "PRO_codDroite") (pin "2") (pinfunction "2_2") (pintype "passive"))
      (node (ref "PRO_codGauche") (pin "1") (pinfunction "1_1") (pintype "passive"))
      (node (ref "PRO_codGauche") (pin "2") (pinfunction "2_2") (pintype "passive"))
      (node (ref "PRO_gyro") (pin "2") (pinfunction "2_2") (pintype "passive"))
      (node (ref "Rpu_sensors") (pin "2") (pinfunction "2_2") (pintype "passive"))
    )
    (net (code "49") (name "5V_Perm") (class "Default")
      (node (ref "PRO_UART1") (pin "1") (pinfunction "1_1") (pintype "passive"))
      (node (ref "PRO_UART1") (pin "2") (pinfunction "2_2") (pintype "passive"))
    )
    (net (code "50") (name "24V") (class "Default")
      (node (ref "PRO_CdDtc1") (pin "2") (pinfunction "2_2") (pintype "passive"))
      (node (ref "PRO_CdDtc2") (pin "2") (pinfunction "2_2") (pintype "passive"))
      (node (ref "PRO_CdDtc3") (pin "2") (pinfunction "2_2") (pintype "passive"))
      (node (ref "PRO_CdDtc4") (pin "2") (pinfunction "2_2") (pintype "passive"))
      (node (ref "PRO_CdDtd6") (pin "2") (pinfunction "2_2") (pintype "passive"))
      (node (ref "PRO_CdDtd7") (pin "2") (pinfunction "2_2") (pintype "passive"))
      (node (ref "PRO_DTc1") (pin "3") (pinfunction "3_3") (pintype "passive"))
      (node (ref "PRO_DTc2") (pin "3") (pinfunction "3_3") (pintype "passive"))
      (node (ref "PRO_DTc3") (pin "3") (pinfunction "3_3") (pintype "passive"))
      (node (ref "PRO_DTc4") (pin "3") (pinfunction "3_3") (pintype "passive"))
      (node (ref "PRO_DTd6") (pin "3") (pinfunction "3_3") (pintype "passive"))
      (node (ref "PRO_DTd7") (pin "3") (pinfunction "3_3") (pintype "passive"))
    )
    (net (code "51") (name "GND") (class "Default")
      (node (ref "PRO_CcodDA") (pin "1") (pinfunction "1_1") (pintype "passive"))
      (node (ref "PRO_CcodDB") (pin "1") (pinfunction "1_1") (pintype "passive"))
      (node (ref "PRO_CcodGA") (pin "1") (pinfunction "1_1") (pintype "passive"))
      (node (ref "PRO_CcodGB") (pin "1") (pinfunction "1_1") (pintype "passive"))
      (node (ref "PRO_CdCan1") (pin "1") (pinfunction "1_1") (pintype "passive"))
      (node (ref "PRO_CdCan2") (pin "1") (pinfunction "1_1") (pintype "passive"))
      (node (ref "PRO_CdGyro") (pin "1") (pinfunction "1_1") (pintype "passive"))
      (node (ref "PRO_CfDTc1") (pin "1") (pinfunction "1_1") (pintype "passive"))
      (node (ref "PRO_CfDTc2") (pin "1") (pinfunction "1_1") (pintype "passive"))
      (node (ref "PRO_CfDTc3") (pin "1") (pinfunction "1_1") (pintype "passive"))
      (node (ref "PRO_CfDTc4") (pin "1") (pinfunction "1_1") (pintype "passive"))
      (node (ref "PRO_CfDTd6") (pin "1") (pinfunction "1_1") (pintype "passive"))
      (node (ref "PRO_CfDTd7") (pin "1") (pinfunction "1_1") (pintype "passive"))
      (node (ref "PRO_Cu1rx") (pin "1") (pinfunction "1_1") (pintype "passive"))
      (node (ref "PRO_DSelftest") (pin "2") (pinfunction "K_2") (pintype "passive"))
      (node (ref "PRO_Derror") (pin "2") (pinfunction "K_2") (pintype "passive"))
      (node (ref "PRO_Motors") (pin "3") (pinfunction "3_3") (pintype "passive"))
      (node (ref "PRO_Motors") (pin "4") (pinfunction "4_4") (pintype "passive"))
      (node (ref "PRO_Rdtc1") (pin "1") (pinfunction "1_1") (pintype "passive"))
      (node (ref "PRO_Rdtc2") (pin "1") (pinfunction "1_1") (pintype "passive"))
      (node (ref "PRO_Rdtc3") (pin "1") (pinfunction "1_1") (pintype "passive"))
      (node (ref "PRO_Rdtc4") (pin "1") (pinfunction "1_1") (pintype "passive"))
      (node (ref "PRO_Rdtd6") (pin "1") (pinfunction "1_1") (pintype "passive"))
      (node (ref "PRO_Rdtd7") (pin "1") (pinfunction "1_1") (pintype "passive"))
      (node (ref "PRO_RdwnWAmI") (pin "1") (pinfunction "1_1") (pintype "passive"))
      (node (ref "PRO_STM32F4DISCOVERY") (pin "1") (pinfunction "GND_1") (pintype "passive"))
      (node (ref "PRO_STM32F4DISCOVERY") (pin "100") (pinfunction "GND_100") (pintype "passive"))
      (node (ref "PRO_STM32F4DISCOVERY") (pin "2") (pinfunction "GND_2") (pintype "passive"))
      (node (ref "PRO_STM32F4DISCOVERY") (pin "23") (pinfunction "GND_23") (pintype "passive"))
      (node (ref "PRO_STM32F4DISCOVERY") (pin "49") (pinfunction "GND_49") (pintype "passive"))
      (node (ref "PRO_STM32F4DISCOVERY") (pin "5") (pinfunction "GND_5") (pintype "passive"))
      (node (ref "PRO_STM32F4DISCOVERY") (pin "50") (pinfunction "GND_50") (pintype "passive"))
      (node (ref "PRO_STM32F4DISCOVERY") (pin "51") (pinfunction "GND_51") (pintype "passive"))
      (node (ref "PRO_STM32F4DISCOVERY") (pin "52") (pinfunction "GND_52") (pintype "passive"))
      (node (ref "PRO_STM32F4DISCOVERY") (pin "99") (pinfunction "GND_99") (pintype "passive"))
      (node (ref "PRO_UART1") (pin "5") (pinfunction "5_5") (pintype "passive"))
      (node (ref "PRO_UART1") (pin "6") (pinfunction "6_6") (pintype "passive"))
      (node (ref "PRO_UART2") (pin "1") (pinfunction "1_1") (pintype "passive"))
      (node (ref "PRO_Ucan") (pin "2") (pinfunction "VSS_2") (pintype "power_in"))
      (node (ref "PRO_Ucan") (pin "8") (pinfunction "RS_8") (pintype "input"))
      (node (ref "PRO_codDroite") (pin "5") (pinfunction "5_5") (pintype "passive"))
      (node (ref "PRO_codDroite") (pin "6") (pinfunction "6_6") (pintype "passive"))
      (node (ref "PRO_codGauche") (pin "5") (pinfunction "5_5") (pintype "passive"))
      (node (ref "PRO_codGauche") (pin "6") (pinfunction "6_6") (pintype "passive"))
      (node (ref "PRO_currentMot") (pin "1") (pinfunction "1_1") (pintype "passive"))
      (node (ref "PRO_gyro") (pin "1") (pinfunction "1_1") (pintype "passive"))
      (node (ref "RFU") (pin "1") (pinfunction "1_1") (pintype "passive"))
      (node (ref "st_i_am_p") (pin "1") (pinfunction "1_1") (pintype "passive"))
    )
    (net (code "52") (name "GND_24") (class "Default")
      (node (ref "MOS_Capt") (pin "2") (pinfunction "S_2") (pintype "passive"))
      (node (ref "PRO_CdDtc1") (pin "1") (pinfunction "1_1") (pintype "passive"))
      (node (ref "PRO_CdDtc2") (pin "1") (pinfunction "1_1") (pintype "passive"))
      (node (ref "PRO_CdDtc3") (pin "1") (pinfunction "1_1") (pintype "passive"))
      (node (ref "PRO_CdDtc4") (pin "1") (pinfunction "1_1") (pintype "passive"))
      (node (ref "PRO_CdDtd6") (pin "1") (pinfunction "1_1") (pintype "passive"))
      (node (ref "PRO_CdDtd7") (pin "1") (pinfunction "1_1") (pintype "passive"))
      (node (ref "PRO_DTd6") (pin "1") (pinfunction "1_1") (pintype "passive"))
      (node (ref "PRO_DTd7") (pin "1") (pinfunction "1_1") (pintype "passive"))
    )
    (net (code "53") (name "GND_capt") (class "Default")
      (node (ref "MOS_Capt") (pin "3") (pinfunction "D_3") (pintype "passive"))
      (node (ref "PRO_DTc1") (pin "1") (pinfunction "1_1") (pintype "passive"))
      (node (ref "PRO_DTc2") (pin "1") (pinfunction "1_1") (pintype "passive"))
      (node (ref "PRO_DTc3") (pin "1") (pinfunction "1_1") (pintype "passive"))
      (node (ref "PRO_DTc4") (pin "1") (pinfunction "1_1") (pintype "passive"))
    )
    (net (code "54") (name "Net-(PRO_DSelftest-A)") (class "Default")
      (node (ref "PRO_DSelftest") (pin "1") (pinfunction "A_1") (pintype "passive"))
      (node (ref "PRO_Rdselftest") (pin "2") (pinfunction "2_2") (pintype "passive"))
    )
    (net (code "55") (name "Net-(PRO_DTc1-Pad2)") (class "Default")
      (node (ref "PRO_DTc1") (pin "2") (pinfunction "2_2") (pintype "passive"))
      (node (ref "PRO_Rdtc1") (pin "2") (pinfunction "2_2") (pintype "passive"))
      (node (ref "PRO_RfDTc1") (pin "1") (pinfunction "1_1") (pintype "passive"))
    )
    (net (code "56") (name "Net-(PRO_DTc2-Pad2)") (class "Default")
      (node (ref "PRO_DTc2") (pin "2") (pinfunction "2_2") (pintype "passive"))
      (node (ref "PRO_Rdtc2") (pin "2") (pinfunction "2_2") (pintype "passive"))
      (node (ref "PRO_RfDTc2") (pin "1") (pinfunction "1_1") (pintype "passive"))
    )
    (net (code "57") (name "Net-(PRO_DTc3-Pad2)") (class "Default")
      (node (ref "PRO_DTc3") (pin "2") (pinfunction "2_2") (pintype "passive"))
      (node (ref "PRO_Rdtc3") (pin "2") (pinfunction "2_2") (pintype "passive"))
      (node (ref "PRO_RfDTc3") (pin "1") (pinfunction "1_1") (pintype "passive"))
    )
    (net (code "58") (name "Net-(PRO_DTc4-Pad2)") (class "Default")
      (node (ref "PRO_DTc4") (pin "2") (pinfunction "2_2") (pintype "passive"))
      (node (ref "PRO_Rdtc4") (pin "2") (pinfunction "2_2") (pintype "passive"))
      (node (ref "PRO_RfDTc4") (pin "1") (pinfunction "1_1") (pintype "passive"))
    )
    (net (code "59") (name "Net-(PRO_DTd6-Pad2)") (class "Default")
      (node (ref "PRO_DTd6") (pin "2") (pinfunction "2_2") (pintype "passive"))
      (node (ref "PRO_Rdtd6") (pin "2") (pinfunction "2_2") (pintype "passive"))
      (node (ref "PRO_RfDTd6") (pin "1") (pinfunction "1_1") (pintype "passive"))
    )
    (net (code "60") (name "Net-(PRO_DTd7-Pad2)") (class "Default")
      (node (ref "PRO_DTd7") (pin "2") (pinfunction "2_2") (pintype "passive"))
      (node (ref "PRO_Rdtd7") (pin "2") (pinfunction "2_2") (pintype "passive"))
      (node (ref "PRO_RfDTd7") (pin "1") (pinfunction "1_1") (pintype "passive"))
    )
    (net (code "61") (name "Net-(PRO_Derror-A)") (class "Default")
      (node (ref "PRO_Derror") (pin "1") (pinfunction "A_1") (pintype "passive"))
      (node (ref "PRO_Rderror") (pin "2") (pinfunction "2_2") (pintype "passive"))
    )
    (net (code "62") (name "Net-(PRO_RCodDA-Pad2)") (class "Default")
      (node (ref "PRO_RCodDA") (pin "2") (pinfunction "2_2") (pintype "passive"))
      (node (ref "PRO_codDroite") (pin "4") (pinfunction "4_4") (pintype "passive"))
    )
    (net (code "63") (name "Net-(PRO_RCodDB-Pad2)") (class "Default")
      (node (ref "PRO_RCodDB") (pin "2") (pinfunction "2_2") (pintype "passive"))
      (node (ref "PRO_codDroite") (pin "3") (pinfunction "3_3") (pintype "passive"))
    )
    (net (code "64") (name "Net-(PRO_RCodGA-Pad2)") (class "Default")
      (node (ref "PRO_RCodGA") (pin "2") (pinfunction "2_2") (pintype "passive"))
      (node (ref "PRO_codGauche") (pin "4") (pinfunction "4_4") (pintype "passive"))
    )
    (net (code "65") (name "Net-(PRO_RCodGB-Pad2)") (class "Default")
      (node (ref "PRO_RCodGB") (pin "2") (pinfunction "2_2") (pintype "passive"))
      (node (ref "PRO_codGauche") (pin "3") (pinfunction "3_3") (pintype "passive"))
    )
    (net (code "66") (name "Net-(PRO_STM32F4DISCOVERY-PE9{slash}FSMC_D6{slash}TIM1_CH1)") (class "Default")
      (node (ref "PRO_STM32F4DISCOVERY") (pin "27") (pinfunction "PE9/FSMC_D6/TIM1_CH1_27") (pintype "passive"))
      (node (ref "st_i_am_p") (pin "2") (pinfunction "2_2") (pintype "passive"))
    )
    (net (code "67") (name "unconnected-(PRO_STM32F4DISCOVERY-BOOT0{slash}VPP-Pad71)") (class "Default")
      (node (ref "PRO_STM32F4DISCOVERY") (pin "71") (pinfunction "BOOT0/VPP_71") (pintype "passive+no_connect"))
    )
    (net (code "68") (name "unconnected-(PRO_STM32F4DISCOVERY-NC-Pad48)") (class "Default")
      (node (ref "PRO_STM32F4DISCOVERY") (pin "48") (pinfunction "NC_48") (pintype "passive+no_connect"))
    )
    (net (code "69") (name "unconnected-(PRO_STM32F4DISCOVERY-NRST-Pad6)") (class "Default")
      (node (ref "PRO_STM32F4DISCOVERY") (pin "6") (pinfunction "NRST_6") (pintype "passive+no_connect"))
    )
    (net (code "70") (name "unconnected-(PRO_STM32F4DISCOVERY-PA0-WKUP{slash}USART2_CTS{slash}USART4_TX{slash}ETH_MII_CRS{slash}TIM2_CH1_ETR{slash}TIM5_CH1{slash}TIM8_ETR{slash}ADC123_IN0{slash}WKUP-Pad12)") (class "Default")
      (node (ref "PRO_STM32F4DISCOVERY") (pin "12") (pinfunction "PA0-WKUP/USART2_CTS/USART4_TX/ETH_MII_CRS/TIM2_CH1_ETR/TIM5_CH1/TIM8_ETR/ADC123_IN0/WKUP_12") (pintype "passive+no_connect"))
    )
    (net (code "71") (name "unconnected-(PRO_STM32F4DISCOVERY-PA4{slash}SPI1_NSS{slash}SPI3_NSS{slash}USART2_CK{slash}DCMI_HSYNC{slash}OTG_HS_SOF{slash}I2S3_WS{slash}ADC12_IN4{slash}DAC1_OUT-Pad16)") (class "Default")
      (node (ref "PRO_STM32F4DISCOVERY") (pin "16") (pinfunction "PA4/SPI1_NSS/SPI3_NSS/USART2_CK/DCMI_HSYNC/OTG_HS_SOF/I2S3_WS/ADC12_IN4/DAC1_OUT_16") (pintype "passive+no_connect"))
    )
    (net (code "72") (name "unconnected-(PRO_STM32F4DISCOVERY-PA5{slash}SPI1_SCK{slash}OTG_HS_ULPI_CK{slash}TIM2_CH1_ETR{slash}TIM8_CHIN{slash}ADC12_IN5{slash}DAC2_OUT-Pad15)") (class "Default")
      (node (ref "PRO_STM32F4DISCOVERY") (pin "15") (pinfunction "PA5/SPI1_SCK/OTG_HS_ULPI_CK/TIM2_CH1_ETR/TIM8_CHIN/ADC12_IN5/DAC2_OUT_15") (pintype "passive+no_connect"))
    )
    (net (code "73") (name "unconnected-(PRO_STM32F4DISCOVERY-PA6{slash}SPI1_MISO{slash}TIM8_BKIN{slash}TIM13_CH1{slash}DCMI_PIXCLK{slash}TIM3_CH1{slash}TIM1_BKIN{slash}ADC12_IN6-Pad18)") (class "Default")
      (node (ref "PRO_STM32F4DISCOVERY") (pin "18") (pinfunction "PA6/SPI1_MISO/TIM8_BKIN/TIM13_CH1/DCMI_PIXCLK/TIM3_CH1/TIM1_BKIN/ADC12_IN6_18") (pintype "passive+no_connect"))
    )
    (net (code "74") (name "unconnected-(PRO_STM32F4DISCOVERY-PA7{slash}SPI1_MOSI{slash}TIM8_CH1N{slash}TIM14_CH1TIM3_CH2{slash}ETH_MII_RX_DV{slash}TIM1_CH1N{slash}RMII_CRS_DV{slash}ADC12_IN7-Pad17)") (class "Default")
      (node (ref "PRO_STM32F4DISCOVERY") (pin "17") (pinfunction "PA7/SPI1_MOSI/TIM8_CH1N/TIM14_CH1TIM3_CH2/ETH_MII_RX_DV/TIM1_CH1N/RMII_CRS_DV/ADC12_IN7_17") (pintype "passive+no_connect"))
    )
    (net (code "75") (name "unconnected-(PRO_STM32F4DISCOVERY-PA8{slash}MCO1{slash}USART1_CK{slash}TIM1_CH1{slash}I2C3_SCL{slash}OTG_FS_SOF-Pad93)") (class "Default")
      (node (ref "PRO_STM32F4DISCOVERY") (pin "93") (pinfunction "PA8/MCO1/USART1_CK/TIM1_CH1/I2C3_SCL/OTG_FS_SOF_93") (pintype "passive+no_connect"))
    )
    (net (code "76") (name "unconnected-(PRO_STM32F4DISCOVERY-PA9{slash}USART1_TX{slash}TIM1_CH2{slash}I2C3_SMBA{slash}DCMI_D0{slash}OTG_FS_VBUS-Pad94)") (class "Default")
      (node (ref "PRO_STM32F4DISCOVERY") (pin "94") (pinfunction "PA9/USART1_TX/TIM1_CH2/I2C3_SMBA/DCMI_D0/OTG_FS_VBUS_94") (pintype "passive+no_connect"))
    )
    (net (code "77") (name "unconnected-(PRO_STM32F4DISCOVERY-PA10{slash}USART1_RX{slash}TIM1_CH3{slash}OTG_FS_ID{slash}DCMI_D1-Pad91)") (class "Default")
      (node (ref "PRO_STM32F4DISCOVERY") (pin "91") (pinfunction "PA10/USART1_RX/TIM1_CH3/OTG_FS_ID/DCMI_D1_91") (pintype "passive+no_connect"))
    )
    (net (code "78") (name "unconnected-(PRO_STM32F4DISCOVERY-PA13{slash}JTMS_SWDIO-Pad92)") (class "Default")
      (node (ref "PRO_STM32F4DISCOVERY") (pin "92") (pinfunction "PA13/JTMS_SWDIO_92") (pintype "passive+no_connect"))
    )
    (net (code "79") (name "unconnected-(PRO_STM32F4DISCOVERY-PA14{slash}JTCK_SWCLK-Pad89)") (class "Default")
      (node (ref "PRO_STM32F4DISCOVERY") (pin "89") (pinfunction "PA14/JTCK_SWCLK_89") (pintype "passive+no_connect"))
    )
    (net (code "80") (name "unconnected-(PRO_STM32F4DISCOVERY-PB2-Pad24)") (class "Default")
      (node (ref "PRO_STM32F4DISCOVERY") (pin "24") (pinfunction "PB2_24") (pintype "passive+no_connect"))
    )
    (net (code "81") (name "unconnected-(PRO_STM32F4DISCOVERY-PB3{slash}JTDO{slash}TRACESWO{slash}SPI3_SCK{slash}I2S3_CK{slash}TIM2_CH2{slash}SPI1_SCK-Pad78)") (class "Default")
      (node (ref "PRO_STM32F4DISCOVERY") (pin "78") (pinfunction "PB3/JTDO/TRACESWO/SPI3_SCK/I2S3_CK/TIM2_CH2/SPI1_SCK_78") (pintype "passive+no_connect"))
    )
    (net (code "82") (name "unconnected-(PRO_STM32F4DISCOVERY-PB10{slash}SPI2_SCK{slash}I2S2_CK{slash}I2C2_SCL{slash}USART3_TX{slash}OTG_HS_ULPI_D3{slash}ETH_MII_RX_ER{slash}OTG_HS_SCL{slash}TIM2_CH3-Pad34)") (class "Default")
      (node (ref "PRO_STM32F4DISCOVERY") (pin "34") (pinfunction "PB10/SPI2_SCK/I2S2_CK/I2C2_SCL/USART3_TX/OTG_HS_ULPI_D3/ETH_MII_RX_ER/OTG_HS_SCL/TIM2_CH3_34") (pintype "passive+no_connect"))
    )
    (net (code "83") (name "unconnected-(PRO_STM32F4DISCOVERY-PB11{slash}I2C2_SDA{slash}USART3_RX{slash}OTG_HS_ULPI_D4{slash}ETH_RMII_TX_EN{slash}ETH_MII_TX_EN{slash}OTG_HS_SDA{slash}TIM2_CH4-Pad35)") (class "Default")
      (node (ref "PRO_STM32F4DISCOVERY") (pin "35") (pinfunction "PB11/I2C2_SDA/USART3_RX/OTG_HS_ULPI_D4/ETH_RMII_TX_EN/ETH_MII_TX_EN/OTG_HS_SDA/TIM2_CH4_35") (pintype "passive+no_connect"))
    )
    (net (code "84") (name "unconnected-(PRO_STM32F4DISCOVERY-PC0{slash}OTG_HS_ULPI_STP{slash}ADC123_IN10-Pad8)") (class "Default")
      (node (ref "PRO_STM32F4DISCOVERY") (pin "8") (pinfunction "PC0/OTG_HS_ULPI_STP/ADC123_IN10_8") (pintype "passive+no_connect"))
    )
    (net (code "85") (name "unconnected-(PRO_STM32F4DISCOVERY-PC5{slash}ETH_RMII_RX_D1{slash}ETH_MII_RX_D1{slash}ADC12_IN15-Pad19)") (class "Default")
      (node (ref "PRO_STM32F4DISCOVERY") (pin "19") (pinfunction "PC5/ETH_RMII_RX_D1/ETH_MII_RX_D1/ADC12_IN15_19") (pintype "passive+no_connect"))
    )
    (net (code "86") (name "unconnected-(PRO_STM32F4DISCOVERY-PC6{slash}I2S2_MCK{slash}TIM8_CH1{slash}SDIO_D6{slash}USART6_TX{slash}DCMI_D0{slash}TIM3_CH1-Pad97)") (class "Default")
      (node (ref "PRO_STM32F4DISCOVERY") (pin "97") (pinfunction "PC6/I2S2_MCK/TIM8_CH1/SDIO_D6/USART6_TX/DCMI_D0/TIM3_CH1_97") (pintype "passive+no_connect"))
    )
    (net (code "87") (name "unconnected-(PRO_STM32F4DISCOVERY-PC7{slash}I2S3_MCK{slash}TIM8_CH2{slash}SDIO_D7{slash}USART6_RX_DCMI_D1{slash}TIM3_CH2-Pad98)") (class "Default")
      (node (ref "PRO_STM32F4DISCOVERY") (pin "98") (pinfunction "PC7/I2S3_MCK/TIM8_CH2/SDIO_D7/USART6_RX_DCMI_D1/TIM3_CH2_98") (pintype "passive+no_connect"))
    )
    (net (code "88") (name "unconnected-(PRO_STM32F4DISCOVERY-PC10{slash}SPI3_SCK{slash}I2S3_CK{slash}UART4_TX{slash}SDIO_D2{slash}DCMI_D8{slash}USART3_TX-Pad87)") (class "Default")
      (node (ref "PRO_STM32F4DISCOVERY") (pin "87") (pinfunction "PC10/SPI3_SCK/I2S3_CK/UART4_TX/SDIO_D2/DCMI_D8/USART3_TX_87") (pintype "passive+no_connect"))
    )
    (net (code "89") (name "unconnected-(PRO_STM32F4DISCOVERY-PC14{slash}OSC32_IN-Pad59)") (class "Default")
      (node (ref "PRO_STM32F4DISCOVERY") (pin "59") (pinfunction "PC14/OSC32_IN_59") (pintype "passive+no_connect"))
    )
    (net (code "90") (name "unconnected-(PRO_STM32F4DISCOVERY-PC15{slash}OSC32_OUT-Pad60)") (class "Default")
      (node (ref "PRO_STM32F4DISCOVERY") (pin "60") (pinfunction "PC15/OSC32_OUT_60") (pintype "passive+no_connect"))
    )
    (net (code "91") (name "unconnected-(PRO_STM32F4DISCOVERY-PD2{slash}TIM3_ETR{slash}UART5_RXSDIO_CMD{slash}DCMI_D11-Pad84)") (class "Default")
      (node (ref "PRO_STM32F4DISCOVERY") (pin "84") (pinfunction "PD2/TIM3_ETR/UART5_RXSDIO_CMD/DCMI_D11_84") (pintype "passive+no_connect"))
    )
    (net (code "92") (name "unconnected-(PRO_STM32F4DISCOVERY-PD3{slash}FSMC_CLK{slash}USART2_CTS-Pad81)") (class "Default")
      (node (ref "PRO_STM32F4DISCOVERY") (pin "81") (pinfunction "PD3/FSMC_CLK/USART2_CTS_81") (pintype "passive+no_connect"))
    )
    (net (code "93") (name "unconnected-(PRO_STM32F4DISCOVERY-PD4{slash}FSMC_NOE{slash}USART2_RTS-Pad82)") (class "Default")
      (node (ref "PRO_STM32F4DISCOVERY") (pin "82") (pinfunction "PD4/FSMC_NOE/USART2_RTS_82") (pintype "passive+no_connect"))
    )
    (net (code "94") (name "unconnected-(PRO_STM32F4DISCOVERY-PD5{slash}FSMC_NWE{slash}USART2_TX-Pad79)") (class "Default")
      (node (ref "PRO_STM32F4DISCOVERY") (pin "79") (pinfunction "PD5/FSMC_NWE/USART2_TX_79") (pintype "passive+no_connect"))
    )
    (net (code "95") (name "unconnected-(PRO_STM32F4DISCOVERY-PD8{slash}FSMC_D13{slash}USART3_TX-Pad40)") (class "Default")
      (node (ref "PRO_STM32F4DISCOVERY") (pin "40") (pinfunction "PD8/FSMC_D13/USART3_TX_40") (pintype "passive+no_connect"))
    )
    (net (code "96") (name "unconnected-(PRO_STM32F4DISCOVERY-PD9{slash}FSMC_D14{slash}USART3_RX-Pad41)") (class "Default")
      (node (ref "PRO_STM32F4DISCOVERY") (pin "41") (pinfunction "PD9/FSMC_D14/USART3_RX_41") (pintype "passive+no_connect"))
    )
    (net (code "97") (name "unconnected-(PRO_STM32F4DISCOVERY-PE0{slash}TIM4_ETR{slash}FSMC_NBL0{slash}DCMI_D2-Pad67)") (class "Default")
      (node (ref "PRO_STM32F4DISCOVERY") (pin "67") (pinfunction "PE0/TIM4_ETR/FSMC_NBL0/DCMI_D2_67") (pintype "passive+no_connect"))
    )
    (net (code "98") (name "unconnected-(PRO_STM32F4DISCOVERY-PE1{slash}FSMC_NBL1{slash}DCMI_D3-Pad68)") (class "Default")
      (node (ref "PRO_STM32F4DISCOVERY") (pin "68") (pinfunction "PE1/FSMC_NBL1/DCMI_D3_68") (pintype "passive+no_connect"))
    )
    (net (code "99") (name "unconnected-(PRO_STM32F4DISCOVERY-PE2{slash}TRACECLK{slash}FSMC_A23{slash}ETH_MII_TXD3-Pad65)") (class "Default")
      (node (ref "PRO_STM32F4DISCOVERY") (pin "65") (pinfunction "PE2/TRACECLK/FSMC_A23/ETH_MII_TXD3_65") (pintype "passive+no_connect"))
    )
    (net (code "100") (name "unconnected-(PRO_STM32F4DISCOVERY-PE3{slash}TRACED0{slash}FSMC_A19-Pad66)") (class "Default")
      (node (ref "PRO_STM32F4DISCOVERY") (pin "66") (pinfunction "PE3/TRACED0/FSMC_A19_66") (pintype "passive+no_connect"))
    )
    (net (code "101") (name "unconnected-(PRO_STM32F4DISCOVERY-PE4{slash}TRACED1{slash}FSMC_A20{slash}DCMI_D4-Pad63)") (class "Default")
      (node (ref "PRO_STM32F4DISCOVERY") (pin "63") (pinfunction "PE4/TRACED1/FSMC_A20/DCMI_D4_63") (pintype "passive+no_connect"))
    )
    (net (code "102") (name "unconnected-(PRO_STM32F4DISCOVERY-PE5{slash}TRACED2{slash}FSMC_A21{slash}TIM9_CH1{slash}DCMI_D6-Pad64)") (class "Default")
      (node (ref "PRO_STM32F4DISCOVERY") (pin "64") (pinfunction "PE5/TRACED2/FSMC_A21/TIM9_CH1/DCMI_D6_64") (pintype "passive+no_connect"))
    )
    (net (code "103") (name "unconnected-(PRO_STM32F4DISCOVERY-PE6{slash}TRACED3{slash}FSMC_A22{slash}TIM9_CH2{slash}DCMI_D7-Pad61)") (class "Default")
      (node (ref "PRO_STM32F4DISCOVERY") (pin "61") (pinfunction "PE6/TRACED3/FSMC_A22/TIM9_CH2/DCMI_D7_61") (pintype "passive+no_connect"))
    )
    (net (code "104") (name "unconnected-(PRO_STM32F4DISCOVERY-PE7{slash}FSMC_D4{slash}TIM1_ETR-Pad25)") (class "Default")
      (node (ref "PRO_STM32F4DISCOVERY") (pin "25") (pinfunction "PE7/FSMC_D4/TIM1_ETR_25") (pintype "passive+no_connect"))
    )
    (net (code "105") (name "unconnected-(PRO_STM32F4DISCOVERY-PE8{slash}FSMC_D5{slash}TIM1_CH1N-Pad26)") (class "Default")
      (node (ref "PRO_STM32F4DISCOVERY") (pin "26") (pinfunction "PE8/FSMC_D5/TIM1_CH1N_26") (pintype "passive+no_connect"))
    )
    (net (code "106") (name "unconnected-(PRO_STM32F4DISCOVERY-PH0{slash}OSC_IN-Pad57)") (class "Default")
      (node (ref "PRO_STM32F4DISCOVERY") (pin "57") (pinfunction "PH0/OSC_IN_57") (pintype "passive+no_connect"))
    )
    (net (code "107") (name "unconnected-(PRO_STM32F4DISCOVERY-PH1{slash}OSC_OUT-Pad58)") (class "Default")
      (node (ref "PRO_STM32F4DISCOVERY") (pin "58") (pinfunction "PH1/OSC_OUT_58") (pintype "passive+no_connect"))
    )
    (net (code "108") (name "unconnected-(PRO_STM32F4DISCOVERY-VDD-Pad3)") (class "Default")
      (node (ref "PRO_STM32F4DISCOVERY") (pin "3") (pinfunction "VDD_3") (pintype "passive+no_connect"))
    )
    (net (code "109") (name "unconnected-(PRO_STM32F4DISCOVERY-VDD-Pad4)") (class "Default")
      (node (ref "PRO_STM32F4DISCOVERY") (pin "4") (pinfunction "VDD_4") (pintype "passive+no_connect"))
    )
    (net (code "110") (name "unconnected-(PRO_STM32F4DISCOVERY-VDD-Pad72)") (class "Default")
      (node (ref "PRO_STM32F4DISCOVERY") (pin "72") (pinfunction "VDD_72") (pintype "passive+no_connect"))
    )
    (net (code "111") (name "unconnected-(PRO_Ucan-VREF-Pad5)") (class "Default")
      (node (ref "PRO_Ucan") (pin "5") (pinfunction "VREF_5") (pintype "output+no_connect"))
    )
  )
)
